# SCH_AP-Wind-sensor.net
KiCad netlist of a schematic drawn in EasyEDA
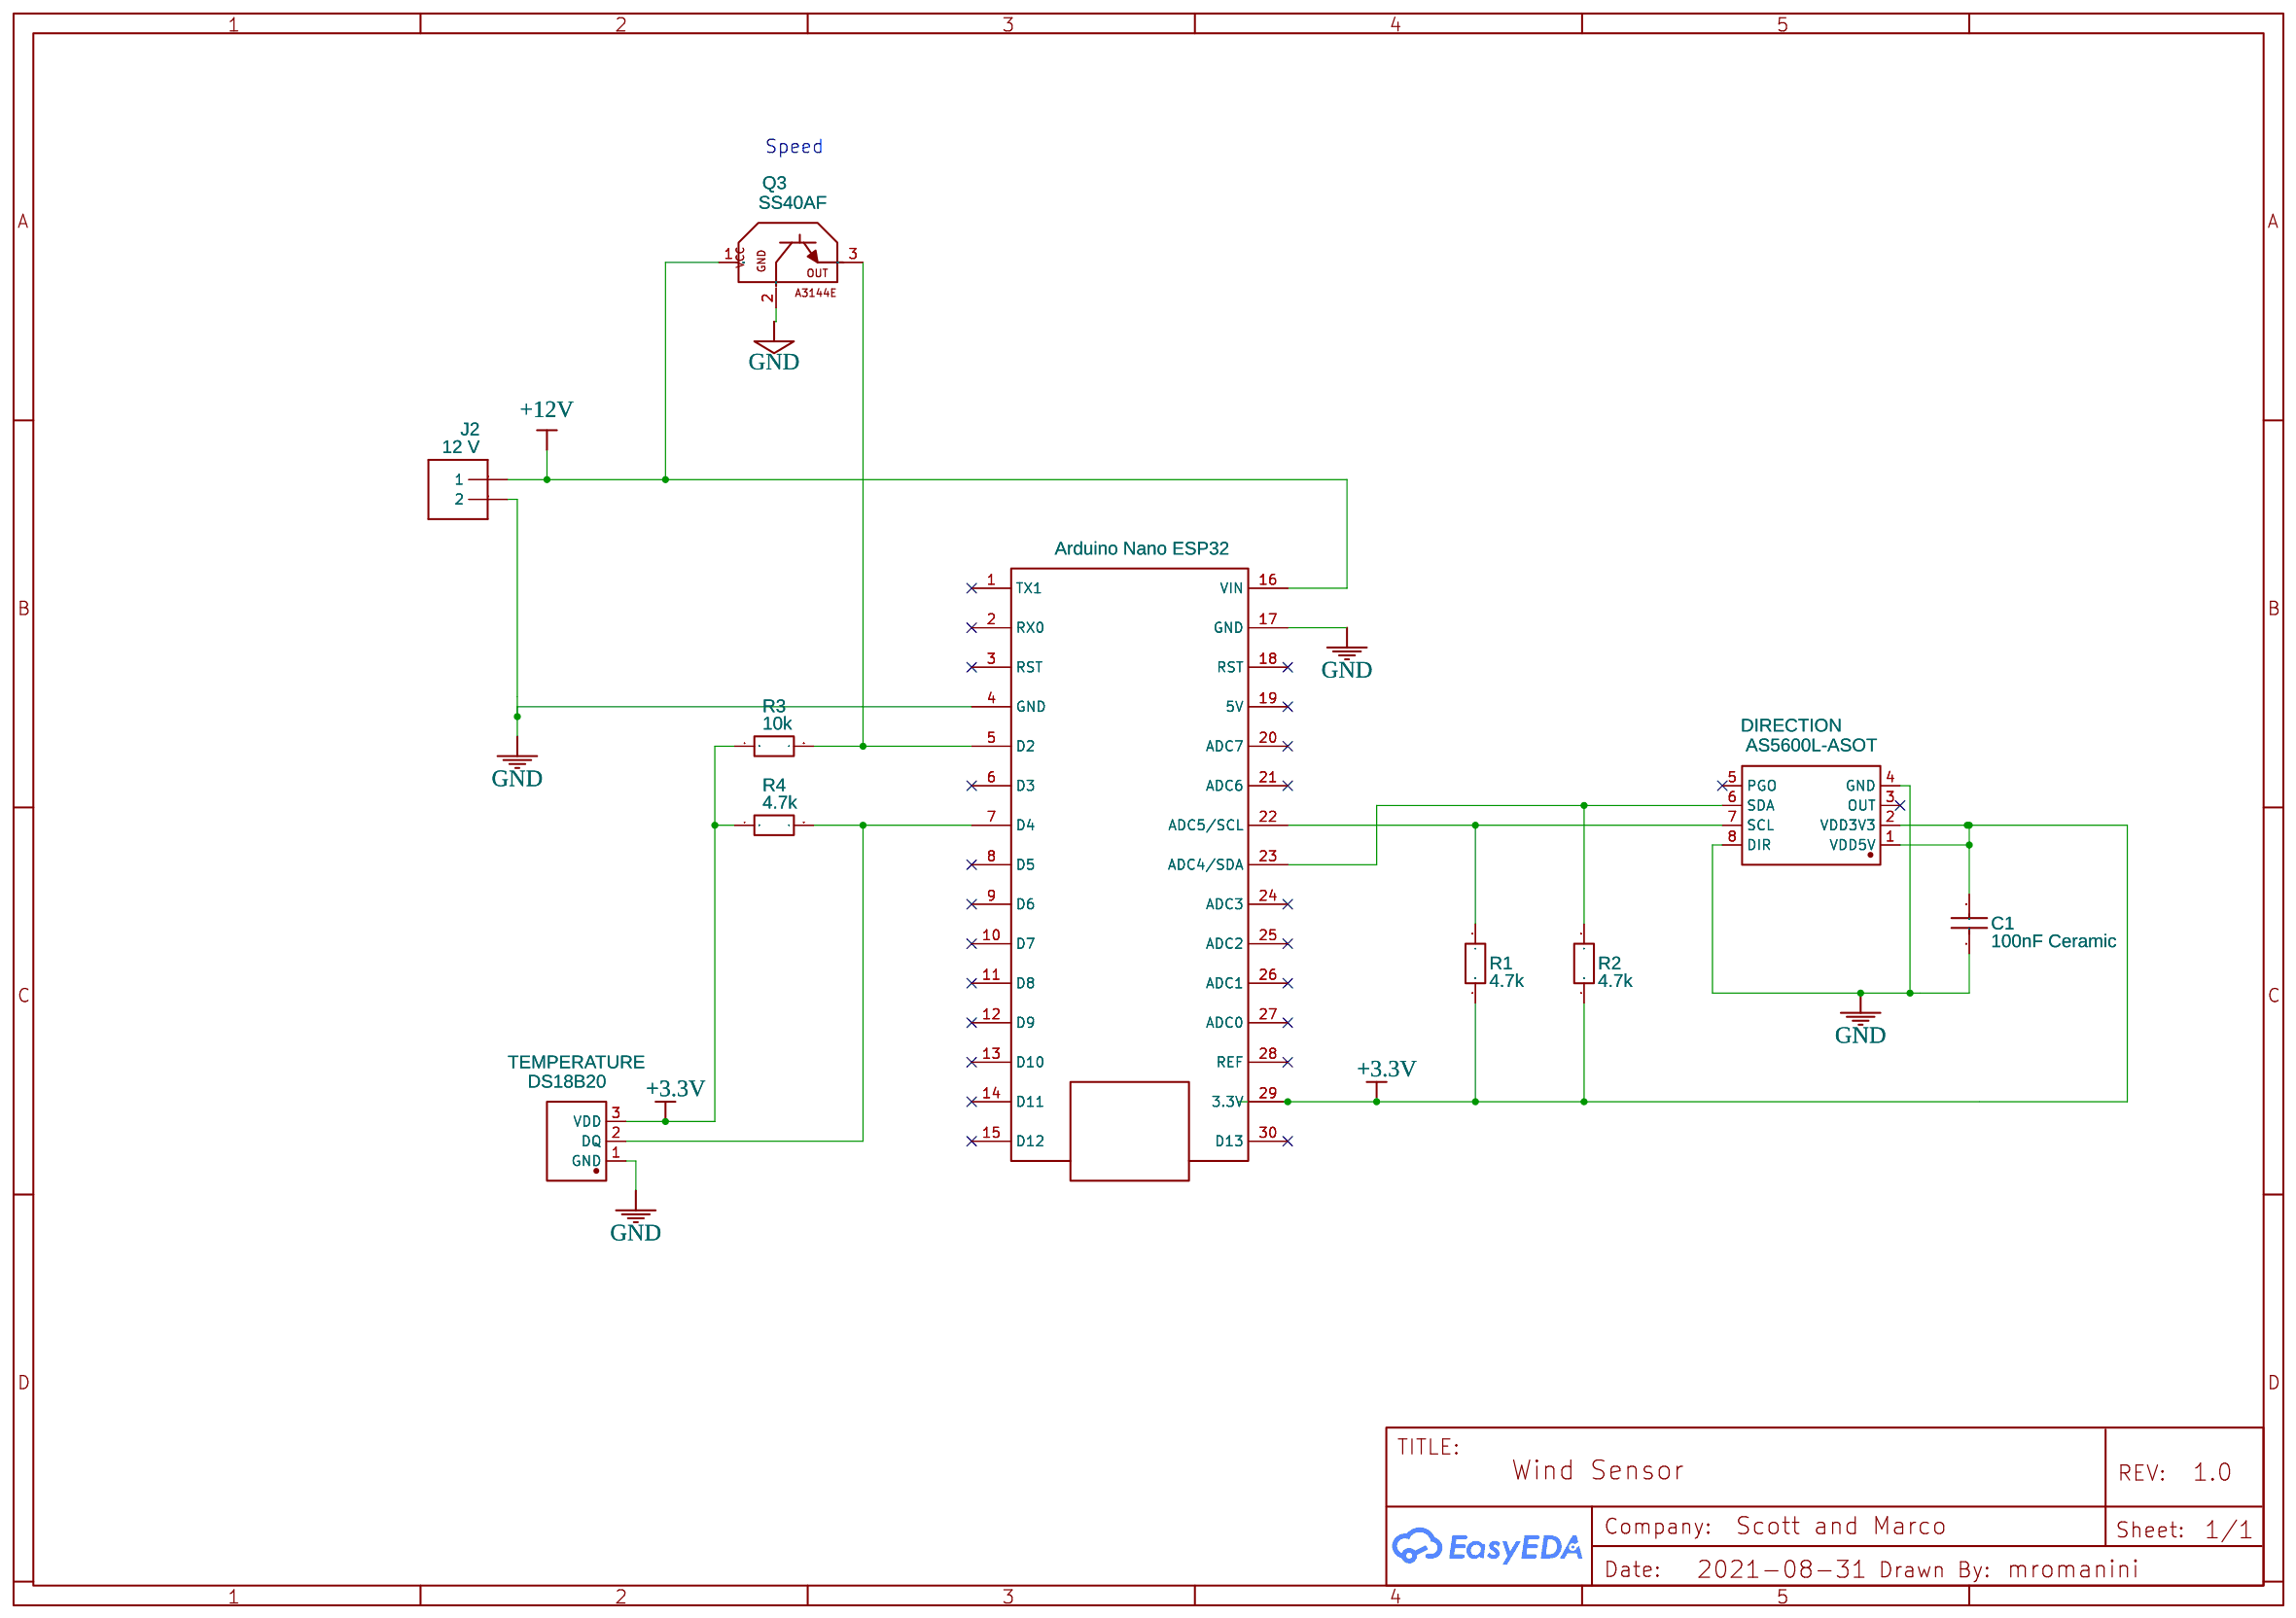
[diagram p0: schematic sheet]

(export (version "E")
  (design (tool "Eeschema 10.0.6"))
  (components
    (comp (ref "C1")
      (value "100nF Ceramic")
      (fields (field (name "Manufacturer Part") "Capacitor_Ceramic"))
      (libsource (lib "") (part "Capacitor_Ceramic"))
    )
    (comp (ref "DIRECTION")
      (value "AS5600L-ASOT")
      (fields (field (name "Manufacturer") "美国AMS"))
      (libsource (lib "") (part "AS5600L-ASOM"))
    )
    (comp (ref "J2") (value "12 V") (libsource (lib "") (part "TERMBLOCK_1X2-3.5MM")))
    (comp (ref "Q3")
      (value "SS40AF")
      (fields (field (name "Manufacturer") "Honeywell"))
      (libsource (lib "") (part "A3144E_HALLSENSOR_COPY"))
    )
    (comp (ref "R1") (value "4.7k") (libsource (lib "") (part "1w resistor")))
    (comp (ref "R2") (value "4.7k") (libsource (lib "") (part "1w resistor")))
    (comp (ref "R3") (value "10k") (libsource (lib "") (part "1w resistor_1")))
    (comp (ref "R4") (value "4.7k") (libsource (lib "") (part "1w resistor_1")))
    (comp (ref "TEMPERATURE")
      (value "DS18B20")
      (fields (field (name "Manufacturer") "Youtai Semiconductor Co., Ltd."))
      (libsource (lib "") (part "DS18B20"))
    )
    (comp (ref "U1") (value "Arduino Nano ESP32") (libsource (lib "") (part "ARDUINO_NANO_R3")))
  )
  (nets
    (net (code "1") (name "+3.3V") (class "Default")
      (node (ref "C1") (pin "1") (pinfunction "1_1") (pintype "unspecified"))
      (node (ref "DIRECTION") (pin "1") (pinfunction "VDD5V_1") (pintype "unspecified"))
      (node (ref "DIRECTION") (pin "2") (pinfunction "VDD3V3_2") (pintype "unspecified"))
      (node (ref "R1") (pin "1") (pinfunction "2_1") (pintype "unspecified"))
      (node (ref "R2") (pin "1") (pinfunction "2_1") (pintype "unspecified"))
      (node (ref "R3") (pin "1") (pinfunction "2_1") (pintype "unspecified"))
      (node (ref "R4") (pin "1") (pinfunction "2_1") (pintype "unspecified"))
      (node (ref "TEMPERATURE") (pin "3") (pinfunction "VDD_3") (pintype "unspecified"))
      (node (ref "U1") (pin "29") (pinfunction "3.3V_29") (pintype "unspecified"))
    )
    (net (code "2") (name "+12V") (class "Default")
      (node (ref "J2") (pin "1") (pinfunction "1_1") (pintype "bidirectional"))
      (node (ref "Q3") (pin "1") (pinfunction "Supply_1") (pintype "unspecified"))
      (node (ref "U1") (pin "16") (pinfunction "VIN_16") (pintype "unspecified"))
    )
    (net (code "3") (name "GND") (class "Default")
      (node (ref "C1") (pin "2") (pinfunction "2_2") (pintype "unspecified"))
      (node (ref "DIRECTION") (pin "4") (pinfunction "GND_4") (pintype "unspecified"))
      (node (ref "DIRECTION") (pin "8") (pinfunction "DIR_8") (pintype "unspecified"))
      (node (ref "J2") (pin "2") (pinfunction "2_2") (pintype "bidirectional"))
      (node (ref "Q3") (pin "2") (pinfunction "Ground_2") (pintype "unspecified"))
      (node (ref "TEMPERATURE") (pin "1") (pinfunction "GND_1") (pintype "unspecified"))
      (node (ref "U1") (pin "17") (pinfunction "GND_17") (pintype "unspecified"))
      (node (ref "U1") (pin "4") (pinfunction "GND_4") (pintype "unspecified"))
    )
    (net (code "4") (name "Net-(DIRECTION-SCL)") (class "Default")
      (node (ref "DIRECTION") (pin "7") (pinfunction "SCL_7") (pintype "unspecified"))
      (node (ref "R1") (pin "2") (pinfunction "1_2") (pintype "unspecified"))
      (node (ref "U1") (pin "22") (pinfunction "ADC5/SCL_22") (pintype "unspecified"))
    )
    (net (code "5") (name "Net-(DIRECTION-SDA)") (class "Default")
      (node (ref "DIRECTION") (pin "6") (pinfunction "SDA_6") (pintype "unspecified"))
      (node (ref "R2") (pin "2") (pinfunction "1_2") (pintype "unspecified"))
      (node (ref "U1") (pin "23") (pinfunction "ADC4/SDA_23") (pintype "unspecified"))
    )
    (net (code "6") (name "Net-(Q3-Output)") (class "Default")
      (node (ref "Q3") (pin "3") (pinfunction "Output_3") (pintype "unspecified"))
      (node (ref "R3") (pin "2") (pinfunction "1_2") (pintype "unspecified"))
      (node (ref "U1") (pin "5") (pinfunction "D2_5") (pintype "unspecified"))
    )
    (net (code "7") (name "Net-(R4-1)") (class "Default")
      (node (ref "R4") (pin "2") (pinfunction "1_2") (pintype "unspecified"))
      (node (ref "TEMPERATURE") (pin "2") (pinfunction "DQ_2") (pintype "unspecified"))
      (node (ref "U1") (pin "7") (pinfunction "D4_7") (pintype "unspecified"))
    )
    (net (code "8") (name "unconnected-(DIRECTION-OUT-Pad3)") (class "Default")
      (node (ref "DIRECTION") (pin "3") (pinfunction "OUT_3") (pintype "unspecified+no_connect"))
    )
    (net (code "9") (name "unconnected-(DIRECTION-PGO-Pad5)") (class "Default")
      (node (ref "DIRECTION") (pin "5") (pinfunction "PGO_5") (pintype "unspecified+no_connect"))
    )
    (net (code "10") (name "unconnected-(U1-5V-Pad19)") (class "Default")
      (node (ref "U1") (pin "19") (pinfunction "5V_19") (pintype "unspecified+no_connect"))
    )
    (net (code "11") (name "unconnected-(U1-ADC0-Pad27)") (class "Default")
      (node (ref "U1") (pin "27") (pinfunction "ADC0_27") (pintype "unspecified+no_connect"))
    )
    (net (code "12") (name "unconnected-(U1-ADC1-Pad26)") (class "Default")
      (node (ref "U1") (pin "26") (pinfunction "ADC1_26") (pintype "unspecified+no_connect"))
    )
    (net (code "13") (name "unconnected-(U1-ADC2-Pad25)") (class "Default")
      (node (ref "U1") (pin "25") (pinfunction "ADC2_25") (pintype "unspecified+no_connect"))
    )
    (net (code "14") (name "unconnected-(U1-ADC3-Pad24)") (class "Default")
      (node (ref "U1") (pin "24") (pinfunction "ADC3_24") (pintype "unspecified+no_connect"))
    )
    (net (code "15") (name "unconnected-(U1-ADC6-Pad21)") (class "Default")
      (node (ref "U1") (pin "21") (pinfunction "ADC6_21") (pintype "unspecified+no_connect"))
    )
    (net (code "16") (name "unconnected-(U1-ADC7-Pad20)") (class "Default")
      (node (ref "U1") (pin "20") (pinfunction "ADC7_20") (pintype "unspecified+no_connect"))
    )
    (net (code "17") (name "unconnected-(U1-D3-Pad6)") (class "Default")
      (node (ref "U1") (pin "6") (pinfunction "D3_6") (pintype "unspecified+no_connect"))
    )
    (net (code "18") (name "unconnected-(U1-D5-Pad8)") (class "Default")
      (node (ref "U1") (pin "8") (pinfunction "D5_8") (pintype "unspecified+no_connect"))
    )
    (net (code "19") (name "unconnected-(U1-D6-Pad9)") (class "Default")
      (node (ref "U1") (pin "9") (pinfunction "D6_9") (pintype "unspecified+no_connect"))
    )
    (net (code "20") (name "unconnected-(U1-D7-Pad10)") (class "Default")
      (node (ref "U1") (pin "10") (pinfunction "D7_10") (pintype "unspecified+no_connect"))
    )
    (net (code "21") (name "unconnected-(U1-D8-Pad11)") (class "Default")
      (node (ref "U1") (pin "11") (pinfunction "D8_11") (pintype "unspecified+no_connect"))
    )
    (net (code "22") (name "unconnected-(U1-D9-Pad12)") (class "Default")
      (node (ref "U1") (pin "12") (pinfunction "D9_12") (pintype "unspecified+no_connect"))
    )
    (net (code "23") (name "unconnected-(U1-D10-Pad13)") (class "Default")
      (node (ref "U1") (pin "13") (pinfunction "D10_13") (pintype "unspecified+no_connect"))
    )
    (net (code "24") (name "unconnected-(U1-D11-Pad14)") (class "Default")
      (node (ref "U1") (pin "14") (pinfunction "D11_14") (pintype "unspecified+no_connect"))
    )
    (net (code "25") (name "unconnected-(U1-D12-Pad15)") (class "Default")
      (node (ref "U1") (pin "15") (pinfunction "D12_15") (pintype "unspecified+no_connect"))
    )
    (net (code "26") (name "unconnected-(U1-D13-Pad30)") (class "Default")
      (node (ref "U1") (pin "30") (pinfunction "D13_30") (pintype "unspecified+no_connect"))
    )
    (net (code "27") (name "unconnected-(U1-REF-Pad28)") (class "Default")
      (node (ref "U1") (pin "28") (pinfunction "REF_28") (pintype "unspecified+no_connect"))
    )
    (net (code "28") (name "unconnected-(U1-RST-Pad3)") (class "Default")
      (node (ref "U1") (pin "3") (pinfunction "RST_3") (pintype "unspecified+no_connect"))
    )
    (net (code "29") (name "unconnected-(U1-RST-Pad18)") (class "Default")
      (node (ref "U1") (pin "18") (pinfunction "RST_18") (pintype "unspecified+no_connect"))
    )
    (net (code "30") (name "unconnected-(U1-RX0-Pad2)") (class "Default")
      (node (ref "U1") (pin "2") (pinfunction "RX0_2") (pintype "unspecified+no_connect"))
    )
    (net (code "31") (name "unconnected-(U1-TX1-Pad1)") (class "Default")
      (node (ref "U1") (pin "1") (pinfunction "TX1_1") (pintype "unspecified+no_connect"))
    )
  )
)
